# ESC_30A.net
KiCad netlist of a schematic drawn in Altium Designer
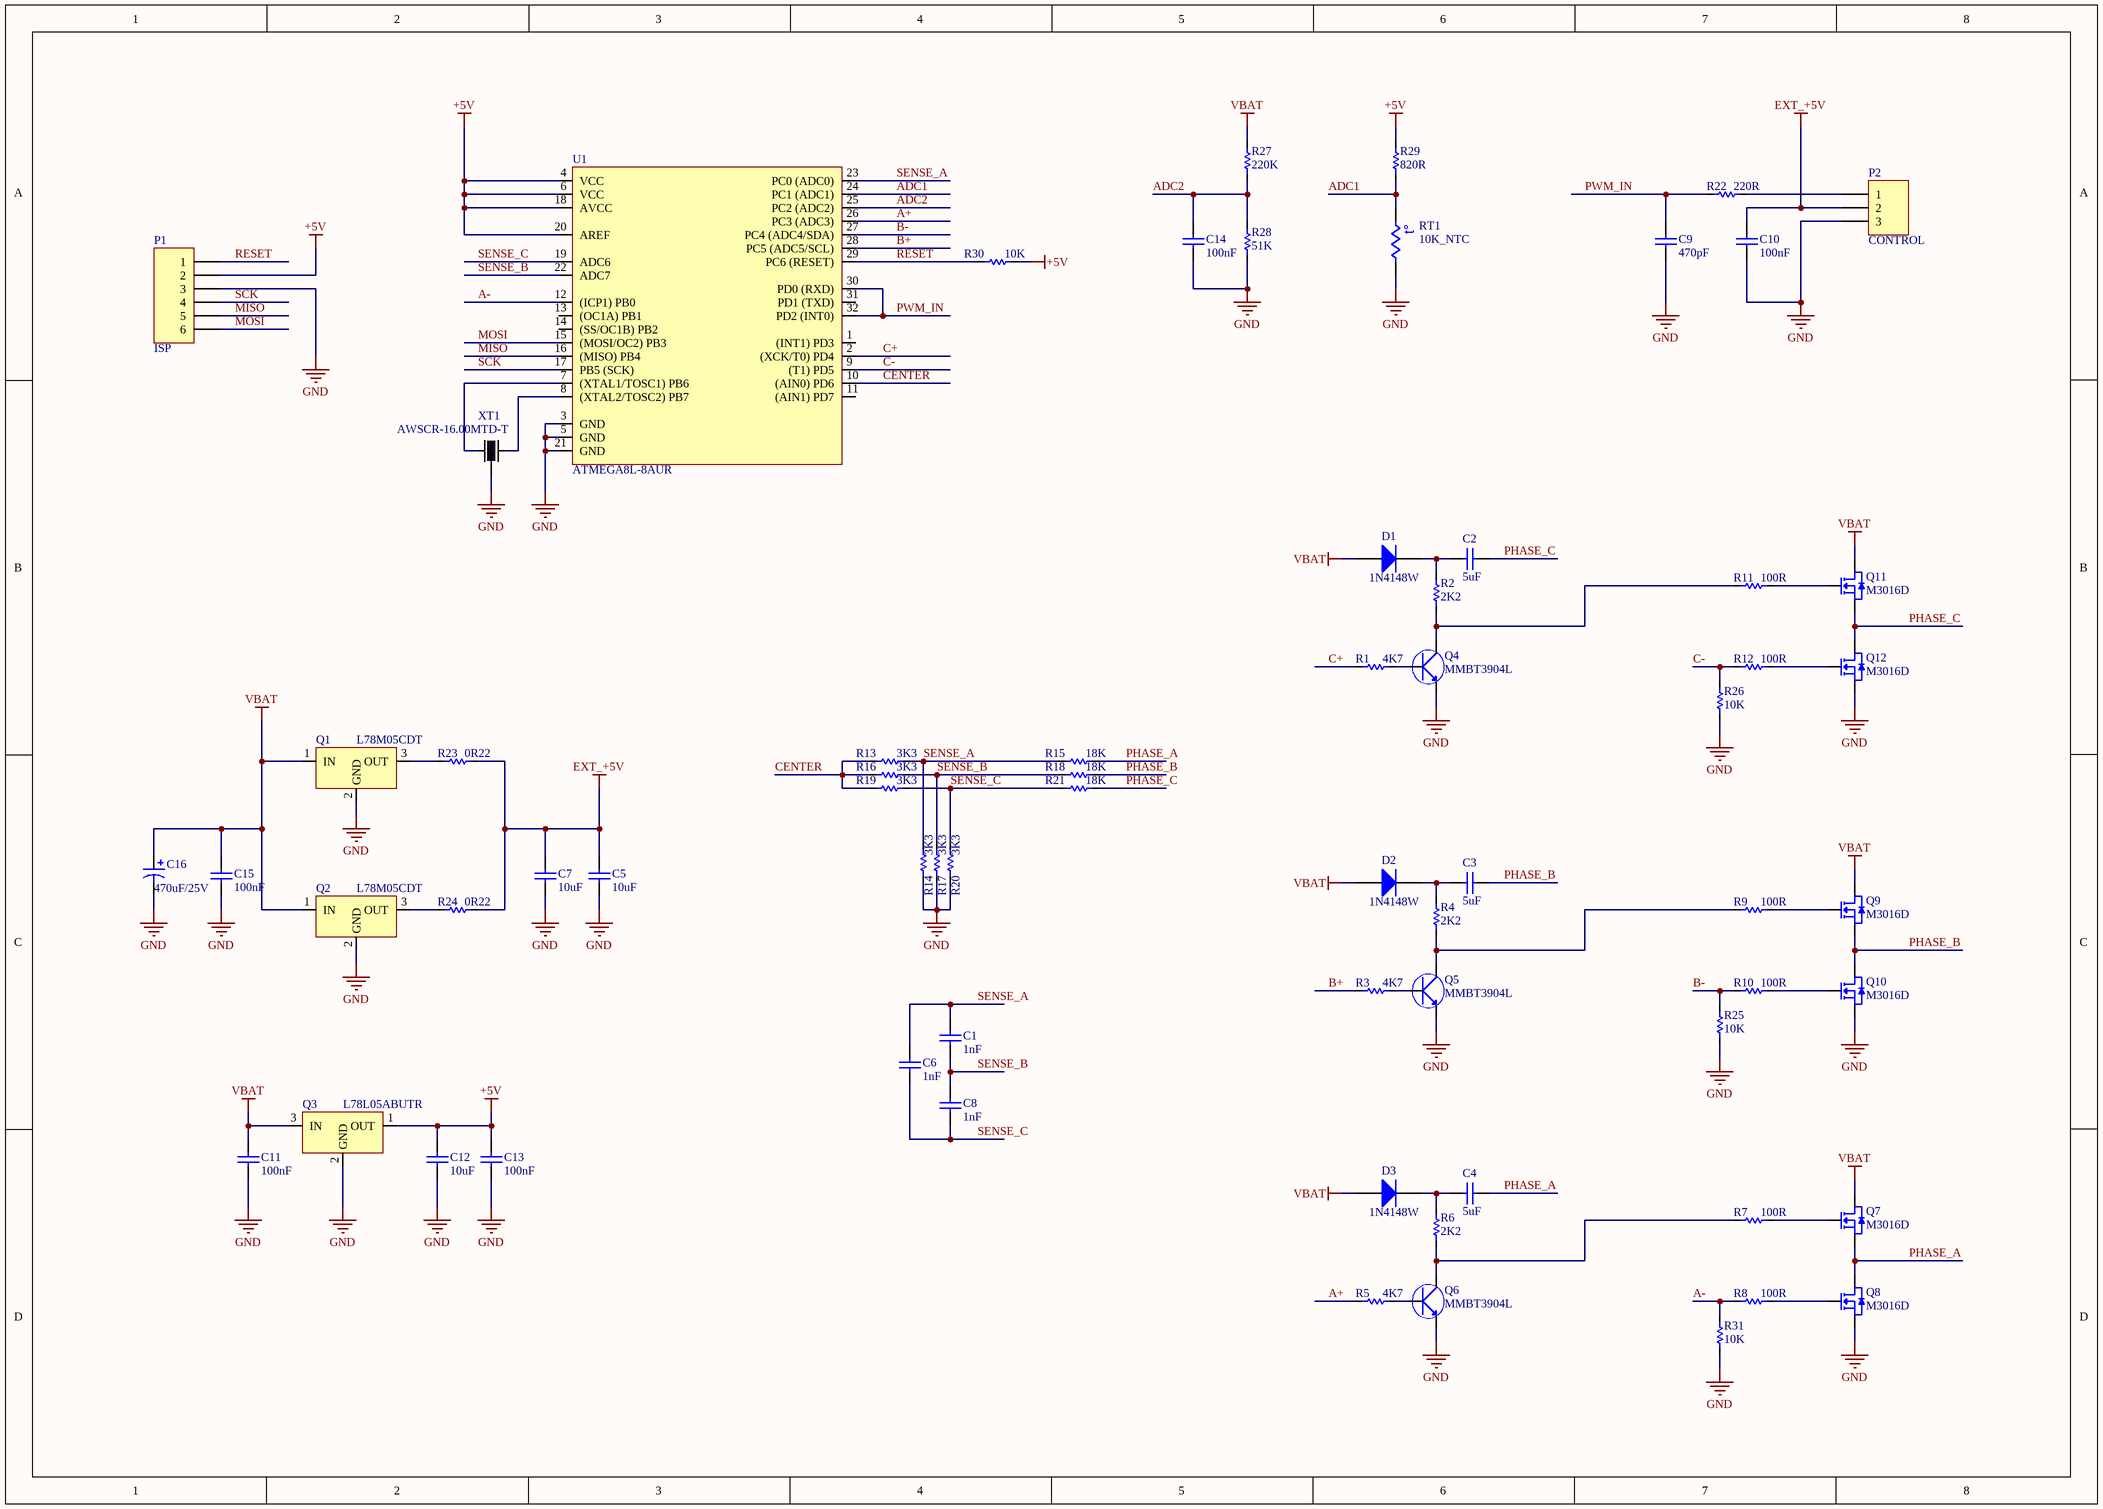
[diagram p0: ESC_30A.SchDoc]

(export (version "E")
  (design (tool "Eeschema 10.0.6"))
  (components
    (comp (ref "C1")
      (value "1nF")
      (footprint "C0603(1608)")
      (description "Capacitor")
      (libsource (lib "Miscellaneous Devices") (part "Cap"))
    )
    (comp (ref "C2")
      (value "5uF")
      (footprint "C1206(3216)")
      (description "Capacitor")
      (libsource (lib "Miscellaneous Devices") (part "Cap"))
    )
    (comp (ref "C3")
      (value "5uF")
      (footprint "C1206(3216)")
      (description "Capacitor")
      (libsource (lib "Miscellaneous Devices") (part "Cap"))
    )
    (comp (ref "C4")
      (value "5uF")
      (footprint "C1206(3216)")
      (description "Capacitor")
      (libsource (lib "Miscellaneous Devices") (part "Cap"))
    )
    (comp (ref "C5")
      (value "10uF")
      (footprint "C1206(3216)")
      (description "Capacitor")
      (libsource (lib "Miscellaneous Devices") (part "Cap"))
    )
    (comp (ref "C6")
      (value "1nF")
      (footprint "C0603(1608)")
      (description "Capacitor")
      (libsource (lib "Miscellaneous Devices") (part "Cap"))
    )
    (comp (ref "C7")
      (value "10uF")
      (footprint "C1206(3216)")
      (description "Capacitor")
      (libsource (lib "Miscellaneous Devices") (part "Cap"))
    )
    (comp (ref "C8")
      (value "1nF")
      (footprint "C0603(1608)")
      (description "Capacitor")
      (libsource (lib "Miscellaneous Devices") (part "Cap"))
    )
    (comp (ref "C9")
      (value "470pF")
      (footprint "C0603(1608)")
      (description "Capacitor")
      (libsource (lib "Miscellaneous Devices") (part "Cap"))
    )
    (comp (ref "C10")
      (value "100nF")
      (footprint "C0603(1608)")
      (description "Capacitor")
      (libsource (lib "Miscellaneous Devices") (part "Cap"))
    )
    (comp (ref "C11")
      (value "100nF")
      (footprint "C0603(1608)")
      (description "Capacitor")
      (libsource (lib "Miscellaneous Devices") (part "Cap"))
    )
    (comp (ref "C12")
      (value "10uF")
      (footprint "C1206(3216)")
      (description "Capacitor")
      (libsource (lib "Miscellaneous Devices") (part "Cap"))
    )
    (comp (ref "C13")
      (value "100nF")
      (footprint "C0603(1608)")
      (description "Capacitor")
      (libsource (lib "Miscellaneous Devices") (part "Cap"))
    )
    (comp (ref "C14")
      (value "100nF")
      (footprint "C0603(1608)")
      (description "Capacitor")
      (libsource (lib "Miscellaneous Devices") (part "Cap"))
    )
    (comp (ref "C15")
      (value "100nF")
      (footprint "C0603(1608)")
      (description "Capacitor")
      (libsource (lib "Miscellaneous Devices") (part "Cap"))
    )
    (comp (ref "C16")
      (value "470uF/25V")
      (footprint "RB.2/.4N")
      (description "CAP ALUM 470UF 20% 25V RADIAL")
      (libsource (lib "Miscellaneous Devices") (part "Cap Pol1"))
    )
    (comp (ref "D1")
      (value "1N4148W")
      (footprint "DIOMELF3515N")
      (description "Default Diode")
      (fields (field (name "PUBLISHER") "Altium Limited"))
      (libsource (lib "Miscellaneous Devices") (part "Diode"))
    )
    (comp (ref "D2")
      (value "1N4148W")
      (footprint "DIOMELF3515N")
      (description "Default Diode")
      (fields (field (name "PUBLISHER") "Altium Limited"))
      (libsource (lib "Miscellaneous Devices") (part "Diode"))
    )
    (comp (ref "D3")
      (value "1N4148W")
      (footprint "DIOMELF3515N")
      (description "Default Diode")
      (fields (field (name "PUBLISHER") "Altium Limited"))
      (libsource (lib "Miscellaneous Devices") (part "Diode"))
    )
    (comp (ref "P1")
      (value "ISP")
      (footprint "SWD-PAD_6")
      (description "Header, 6-Pin")
      (fields (field (name "PUBLISHER") "Altium Limited"))
      (libsource (lib "Miscellaneous Connectors") (part "Header 6"))
    )
    (comp (ref "P2")
      (value "CONTROL")
      (footprint "Pin Header 1x3 TH Pitch 2.54mm")
      (description "Header, 3-Pin")
      (fields (field (name "PUBLISHER") "Altium Limited"))
      (libsource (lib "Miscellaneous Connectors") (part "Header 3"))
    )
    (comp (ref "Q1")
      (value "L78M05CDT")
      (footprint "DPAK229P1010X238-3N")
      (description "IC REG LINEAR 5V 500MA DPAK")
      (libsource (lib "ali_lib") (part "78M05"))
    )
    (comp (ref "Q2")
      (value "L78M05CDT")
      (footprint "DPAK229P1010X238-3N")
      (description "IC REG LINEAR 5V 500MA DPAK")
      (libsource (lib "ali_lib") (part "78M05"))
    )
    (comp (ref "Q3")
      (value "L78L05ABUTR")
      (footprint "SOT89-150P409X160-3N")
      (description "IC REG LINEAR 5V 100MA SOT89-3")
      (libsource (lib "ali_lib") (part "78L05"))
    )
    (comp (ref "Q4")
      (value "MMBT3904L")
      (footprint "SOT23-A")
      (description "TRANS NPN 40V 0.2A SOT23")
      (libsource (lib "ali_lib") (part "TRANS"))
    )
    (comp (ref "Q5")
      (value "MMBT3904L")
      (footprint "SOT23-A")
      (description "TRANS NPN 40V 0.2A SOT23")
      (libsource (lib "ali_lib") (part "TRANS"))
    )
    (comp (ref "Q6")
      (value "MMBT3904L")
      (footprint "SOT23-A")
      (description "TRANS NPN 40V 0.2A SOT23")
      (libsource (lib "ali_lib") (part "TRANS"))
    )
    (comp (ref "Q7")
      (value "M3016D")
      (footprint "DPAK229P1010X238-3N")
      (description "N-Ch 30V Fast Switching MOSFETs")
      (libsource (lib "ali_lib") (part "MOSFET-M3016D"))
    )
    (comp (ref "Q8")
      (value "M3016D")
      (footprint "DPAK229P1010X238-3N")
      (description "N-Ch 30V Fast Switching MOSFETs")
      (libsource (lib "ali_lib") (part "MOSFET-M3016D"))
    )
    (comp (ref "Q9")
      (value "M3016D")
      (footprint "DPAK229P1010X238-3N")
      (description "N-Ch 30V Fast Switching MOSFETs")
      (libsource (lib "ali_lib") (part "MOSFET-M3016D"))
    )
    (comp (ref "Q10")
      (value "M3016D")
      (footprint "DPAK229P1010X238-3N")
      (description "N-Ch 30V Fast Switching MOSFETs")
      (libsource (lib "ali_lib") (part "MOSFET-M3016D"))
    )
    (comp (ref "Q11")
      (value "M3016D")
      (footprint "DPAK229P1010X238-3N")
      (description "N-Ch 30V Fast Switching MOSFETs")
      (libsource (lib "ali_lib") (part "MOSFET-M3016D"))
    )
    (comp (ref "Q12")
      (value "M3016D")
      (footprint "DPAK229P1010X238-3N")
      (description "N-Ch 30V Fast Switching MOSFETs")
      (libsource (lib "ali_lib") (part "MOSFET-M3016D"))
    )
    (comp (ref "R1")
      (value "4K7")
      (footprint "R0603(1608)")
      (description "Resistor")
      (libsource (lib "ali_lib") (part "R"))
    )
    (comp (ref "R2")
      (value "2K2")
      (footprint "R0603(1608)")
      (description "Resistor")
      (libsource (lib "ali_lib") (part "R"))
    )
    (comp (ref "R3")
      (value "4K7")
      (footprint "R0603(1608)")
      (description "Resistor")
      (libsource (lib "ali_lib") (part "R"))
    )
    (comp (ref "R4")
      (value "2K2")
      (footprint "R0603(1608)")
      (description "Resistor")
      (libsource (lib "ali_lib") (part "R"))
    )
    (comp (ref "R5")
      (value "4K7")
      (footprint "R0603(1608)")
      (description "Resistor")
      (libsource (lib "ali_lib") (part "R"))
    )
    (comp (ref "R6")
      (value "2K2")
      (footprint "R0603(1608)")
      (description "Resistor")
      (libsource (lib "ali_lib") (part "R"))
    )
    (comp (ref "R7")
      (value "100R")
      (footprint "R0603(1608)")
      (description "Resistor")
      (libsource (lib "ali_lib") (part "R"))
    )
    (comp (ref "R8")
      (value "100R")
      (footprint "R0603(1608)")
      (description "Resistor")
      (libsource (lib "ali_lib") (part "R"))
    )
    (comp (ref "R9")
      (value "100R")
      (footprint "R0603(1608)")
      (description "Resistor")
      (libsource (lib "ali_lib") (part "R"))
    )
    (comp (ref "R10")
      (value "100R")
      (footprint "R0603(1608)")
      (description "Resistor")
      (libsource (lib "ali_lib") (part "R"))
    )
    (comp (ref "R11")
      (value "100R")
      (footprint "R0603(1608)")
      (description "Resistor")
      (libsource (lib "ali_lib") (part "R"))
    )
    (comp (ref "R12")
      (value "100R")
      (footprint "R0603(1608)")
      (description "Resistor")
      (libsource (lib "ali_lib") (part "R"))
    )
    (comp (ref "R13")
      (value "3K3")
      (footprint "R0603(1608)")
      (description "Resistor")
      (libsource (lib "ali_lib") (part "R"))
    )
    (comp (ref "R14")
      (value "3K3")
      (footprint "R0603(1608)")
      (description "Resistor")
      (libsource (lib "ali_lib") (part "R"))
    )
    (comp (ref "R15")
      (value "18K")
      (footprint "R0603(1608)")
      (description "Resistor")
      (libsource (lib "ali_lib") (part "R"))
    )
    (comp (ref "R16")
      (value "3K3")
      (footprint "R0603(1608)")
      (description "Resistor")
      (libsource (lib "ali_lib") (part "R"))
    )
    (comp (ref "R17")
      (value "3K3")
      (footprint "R0603(1608)")
      (description "Resistor")
      (libsource (lib "ali_lib") (part "R"))
    )
    (comp (ref "R18")
      (value "18K")
      (footprint "R0603(1608)")
      (description "Resistor")
      (libsource (lib "ali_lib") (part "R"))
    )
    (comp (ref "R19")
      (value "3K3")
      (footprint "R0603(1608)")
      (description "Resistor")
      (libsource (lib "ali_lib") (part "R"))
    )
    (comp (ref "R20")
      (value "3K3")
      (footprint "R0603(1608)")
      (description "Resistor")
      (libsource (lib "ali_lib") (part "R"))
    )
    (comp (ref "R21")
      (value "18K")
      (footprint "R0603(1608)")
      (description "Resistor")
      (libsource (lib "ali_lib") (part "R"))
    )
    (comp (ref "R22")
      (value "220R")
      (footprint "R0603(1608)")
      (description "Resistor")
      (libsource (lib "ali_lib") (part "R"))
    )
    (comp (ref "R23")
      (value "0R22")
      (footprint "R0805(2012)")
      (description "Resistor")
      (libsource (lib "ali_lib") (part "R"))
    )
    (comp (ref "R24")
      (value "0R22")
      (footprint "R0805(2012)")
      (description "Resistor")
      (libsource (lib "ali_lib") (part "R"))
    )
    (comp (ref "R25")
      (value "10K")
      (footprint "R0603(1608)")
      (description "Resistor")
      (libsource (lib "ali_lib") (part "R"))
    )
    (comp (ref "R26")
      (value "10K")
      (footprint "R0603(1608)")
      (description "Resistor")
      (libsource (lib "ali_lib") (part "R"))
    )
    (comp (ref "R27")
      (value "220K")
      (footprint "R0603(1608)")
      (description "Resistor")
      (libsource (lib "ali_lib") (part "R"))
    )
    (comp (ref "R28")
      (value "51K")
      (footprint "R0603(1608)")
      (description "Resistor")
      (libsource (lib "ali_lib") (part "R"))
    )
    (comp (ref "R29")
      (value "820R")
      (footprint "R0603(1608)")
      (description "Resistor")
      (libsource (lib "ali_lib") (part "R"))
    )
    (comp (ref "R30")
      (value "10K")
      (footprint "R0603(1608)")
      (description "Resistor")
      (libsource (lib "ali_lib") (part "R"))
    )
    (comp (ref "R31")
      (value "10K")
      (footprint "R0603(1608)")
      (description "Resistor")
      (libsource (lib "ali_lib") (part "R"))
    )
    (comp (ref "RT1")
      (value "10K_NTC")
      (footprint "R0805(2012)")
      (description "Thermistor")
      (fields (field (name "PUBLISHER") "Altium Limited"))
      (libsource (lib "Miscellaneous Devices") (part "Res Thermal"))
    )
    (comp (ref "U1")
      (value "ATMEGA8L-8AUR")
      (footprint "TQFP80P900X900X120-32N")
      (description "IC MCU 8BIT 8KB FLASH 32TQFP")
      (libsource (lib "ali_lib") (part "ATMEGA8L"))
    )
    (comp (ref "XT1")
      (value "AWSCR-16.00MTD-T")
      (footprint "XTAL_AWSCR")
      (description "CER RES 16.0000MHZ 22PF SMD")
      (libsource (lib "ali_lib") (part "XTAL_RESONATOR"))
    )
  )
  (nets
    (net (code "1") (name "+5V") (class "Default")
      (node (ref "C12") (pin "2") (pinfunction "2_2") (pintype "passive"))
      (node (ref "C13") (pin "2") (pinfunction "2_2") (pintype "passive"))
      (node (ref "P1") (pin "2") (pinfunction "2_2") (pintype "passive"))
      (node (ref "Q3") (pin "1") (pinfunction "OUT_1") (pintype "passive"))
      (node (ref "R29") (pin "2") (pinfunction "2_2") (pintype "passive"))
      (node (ref "R30") (pin "2") (pinfunction "2_2") (pintype "passive"))
      (node (ref "U1") (pin "18") (pinfunction "AVCC_18") (pintype "passive"))
      (node (ref "U1") (pin "20") (pinfunction "AREF_20") (pintype "passive"))
      (node (ref "U1") (pin "4") (pinfunction "VCC_4") (pintype "passive"))
      (node (ref "U1") (pin "6") (pinfunction "VCC_6") (pintype "passive"))
    )
    (net (code "2") (name "/A+") (class "Default")
      (node (ref "R5") (pin "1") (pinfunction "1_1") (pintype "passive"))
      (node (ref "U1") (pin "26") (pinfunction "PC3_(ADC3)_26") (pintype "passive"))
    )
    (net (code "3") (name "/A-") (class "Default")
      (node (ref "R31") (pin "1") (pinfunction "1_1") (pintype "passive"))
      (node (ref "R8") (pin "1") (pinfunction "1_1") (pintype "passive"))
      (node (ref "U1") (pin "12") (pinfunction "(ICP1)_PB0_12") (pintype "passive"))
    )
    (net (code "4") (name "/ADC1") (class "Default")
      (node (ref "R29") (pin "1") (pinfunction "1_1") (pintype "passive"))
      (node (ref "RT1") (pin "1") (pinfunction "1_1") (pintype "passive"))
      (node (ref "U1") (pin "24") (pinfunction "PC1_(ADC1)_24") (pintype "passive"))
    )
    (net (code "5") (name "/ADC2") (class "Default")
      (node (ref "C14") (pin "2") (pinfunction "2_2") (pintype "passive"))
      (node (ref "R27") (pin "1") (pinfunction "1_1") (pintype "passive"))
      (node (ref "R28") (pin "2") (pinfunction "2_2") (pintype "passive"))
      (node (ref "U1") (pin "25") (pinfunction "PC2_(ADC2)_25") (pintype "passive"))
    )
    (net (code "6") (name "/B+") (class "Default")
      (node (ref "R3") (pin "1") (pinfunction "1_1") (pintype "passive"))
      (node (ref "U1") (pin "28") (pinfunction "PC5_(ADC5/SCL)_28") (pintype "passive"))
    )
    (net (code "7") (name "/B-") (class "Default")
      (node (ref "R10") (pin "1") (pinfunction "1_1") (pintype "passive"))
      (node (ref "R25") (pin "1") (pinfunction "1_1") (pintype "passive"))
      (node (ref "U1") (pin "27") (pinfunction "PC4_(ADC4/SDA)_27") (pintype "passive"))
    )
    (net (code "8") (name "/C+") (class "Default")
      (node (ref "R1") (pin "1") (pinfunction "1_1") (pintype "passive"))
      (node (ref "U1") (pin "2") (pinfunction "(XCK/T0)_PD4_2") (pintype "passive"))
    )
    (net (code "9") (name "/C-") (class "Default")
      (node (ref "R12") (pin "1") (pinfunction "1_1") (pintype "passive"))
      (node (ref "R26") (pin "1") (pinfunction "1_1") (pintype "passive"))
      (node (ref "U1") (pin "9") (pinfunction "(T1)_PD5_9") (pintype "passive"))
    )
    (net (code "10") (name "/CENTER") (class "Default")
      (node (ref "R13") (pin "1") (pinfunction "1_1") (pintype "passive"))
      (node (ref "R16") (pin "1") (pinfunction "1_1") (pintype "passive"))
      (node (ref "R19") (pin "1") (pinfunction "1_1") (pintype "passive"))
      (node (ref "U1") (pin "10") (pinfunction "(AIN0)_PD6_10") (pintype "passive"))
    )
    (net (code "11") (name "/MISO") (class "Default")
      (node (ref "P1") (pin "5") (pinfunction "5_5") (pintype "passive"))
      (node (ref "U1") (pin "16") (pinfunction "(MISO)_PB4_16") (pintype "passive"))
    )
    (net (code "12") (name "/MOSI") (class "Default")
      (node (ref "P1") (pin "6") (pinfunction "6_6") (pintype "passive"))
      (node (ref "U1") (pin "15") (pinfunction "(MOSI/OC2)_PB3_15") (pintype "passive"))
    )
    (net (code "13") (name "/PHASE_A") (class "Default")
      (node (ref "C4") (pin "1") (pinfunction "1_1") (pintype "passive"))
      (node (ref "Q7") (pin "3") (pinfunction "S_3") (pintype "passive"))
      (node (ref "Q8") (pin "2") (pinfunction "D_2") (pintype "passive"))
      (node (ref "R15") (pin "1") (pinfunction "1_1") (pintype "passive"))
    )
    (net (code "14") (name "/PHASE_B") (class "Default")
      (node (ref "C3") (pin "1") (pinfunction "1_1") (pintype "passive"))
      (node (ref "Q10") (pin "2") (pinfunction "D_2") (pintype "passive"))
      (node (ref "Q9") (pin "3") (pinfunction "S_3") (pintype "passive"))
      (node (ref "R18") (pin "1") (pinfunction "1_1") (pintype "passive"))
    )
    (net (code "15") (name "/PHASE_C") (class "Default")
      (node (ref "C2") (pin "1") (pinfunction "1_1") (pintype "passive"))
      (node (ref "Q11") (pin "3") (pinfunction "S_3") (pintype "passive"))
      (node (ref "Q12") (pin "2") (pinfunction "D_2") (pintype "passive"))
      (node (ref "R21") (pin "1") (pinfunction "1_1") (pintype "passive"))
    )
    (net (code "16") (name "/PWM_IN") (class "Default")
      (node (ref "C9") (pin "2") (pinfunction "2_2") (pintype "passive"))
      (node (ref "R22") (pin "1") (pinfunction "1_1") (pintype "passive"))
      (node (ref "U1") (pin "30") (pinfunction "PD0_(RXD)_30") (pintype "passive"))
      (node (ref "U1") (pin "32") (pinfunction "PD2_(INT0)_32") (pintype "passive"))
    )
    (net (code "17") (name "/RESET") (class "Default")
      (node (ref "P1") (pin "1") (pinfunction "1_1") (pintype "passive"))
      (node (ref "R30") (pin "1") (pinfunction "1_1") (pintype "passive"))
      (node (ref "U1") (pin "29") (pinfunction "PC6_(RESET)_29") (pintype "passive"))
    )
    (net (code "18") (name "/SCK") (class "Default")
      (node (ref "P1") (pin "4") (pinfunction "4_4") (pintype "passive"))
      (node (ref "U1") (pin "17") (pinfunction "PB5_(SCK)_17") (pintype "passive"))
    )
    (net (code "19") (name "/SENSE_A") (class "Default")
      (node (ref "C1") (pin "1") (pinfunction "1_1") (pintype "passive"))
      (node (ref "C6") (pin "1") (pinfunction "1_1") (pintype "passive"))
      (node (ref "R13") (pin "2") (pinfunction "2_2") (pintype "passive"))
      (node (ref "R14") (pin "2") (pinfunction "2_2") (pintype "passive"))
      (node (ref "R15") (pin "2") (pinfunction "2_2") (pintype "passive"))
      (node (ref "U1") (pin "23") (pinfunction "PC0_(ADC0)_23") (pintype "passive"))
    )
    (net (code "20") (name "/SENSE_B") (class "Default")
      (node (ref "C1") (pin "2") (pinfunction "2_2") (pintype "passive"))
      (node (ref "C8") (pin "1") (pinfunction "1_1") (pintype "passive"))
      (node (ref "R16") (pin "2") (pinfunction "2_2") (pintype "passive"))
      (node (ref "R17") (pin "2") (pinfunction "2_2") (pintype "passive"))
      (node (ref "R18") (pin "2") (pinfunction "2_2") (pintype "passive"))
      (node (ref "U1") (pin "22") (pinfunction "ADC7_22") (pintype "passive"))
    )
    (net (code "21") (name "/SENSE_C") (class "Default")
      (node (ref "C6") (pin "2") (pinfunction "2_2") (pintype "passive"))
      (node (ref "C8") (pin "2") (pinfunction "2_2") (pintype "passive"))
      (node (ref "R19") (pin "2") (pinfunction "2_2") (pintype "passive"))
      (node (ref "R20") (pin "2") (pinfunction "2_2") (pintype "passive"))
      (node (ref "R21") (pin "2") (pinfunction "2_2") (pintype "passive"))
      (node (ref "U1") (pin "19") (pinfunction "ADC6_19") (pintype "passive"))
    )
    (net (code "22") (name "EXT_+5V") (class "Default")
      (node (ref "C10") (pin "2") (pinfunction "2_2") (pintype "passive"))
      (node (ref "C5") (pin "2") (pinfunction "2_2") (pintype "passive"))
      (node (ref "C7") (pin "2") (pinfunction "2_2") (pintype "passive"))
      (node (ref "P2") (pin "2") (pinfunction "2_2") (pintype "passive"))
      (node (ref "R23") (pin "2") (pinfunction "2_2") (pintype "passive"))
      (node (ref "R24") (pin "2") (pinfunction "2_2") (pintype "passive"))
    )
    (net (code "23") (name "GND") (class "Default")
      (node (ref "C10") (pin "1") (pinfunction "1_1") (pintype "passive"))
      (node (ref "C11") (pin "1") (pinfunction "1_1") (pintype "passive"))
      (node (ref "C12") (pin "1") (pinfunction "1_1") (pintype "passive"))
      (node (ref "C13") (pin "1") (pinfunction "1_1") (pintype "passive"))
      (node (ref "C14") (pin "1") (pinfunction "1_1") (pintype "passive"))
      (node (ref "C15") (pin "1") (pinfunction "1_1") (pintype "passive"))
      (node (ref "C16") (pin "2") (pinfunction "2_2") (pintype "passive"))
      (node (ref "C5") (pin "1") (pinfunction "1_1") (pintype "passive"))
      (node (ref "C7") (pin "1") (pinfunction "1_1") (pintype "passive"))
      (node (ref "C9") (pin "1") (pinfunction "1_1") (pintype "passive"))
      (node (ref "P1") (pin "3") (pinfunction "3_3") (pintype "passive"))
      (node (ref "P2") (pin "3") (pinfunction "3_3") (pintype "passive"))
      (node (ref "Q1") (pin "2") (pinfunction "GND_2") (pintype "passive"))
      (node (ref "Q10") (pin "3") (pinfunction "S_3") (pintype "passive"))
      (node (ref "Q12") (pin "3") (pinfunction "S_3") (pintype "passive"))
      (node (ref "Q2") (pin "2") (pinfunction "GND_2") (pintype "passive"))
      (node (ref "Q3") (pin "2") (pinfunction "GND_2") (pintype "passive"))
      (node (ref "Q4") (pin "2") (pinfunction "E_2") (pintype "passive"))
      (node (ref "Q5") (pin "2") (pinfunction "E_2") (pintype "passive"))
      (node (ref "Q6") (pin "2") (pinfunction "E_2") (pintype "passive"))
      (node (ref "Q8") (pin "3") (pinfunction "S_3") (pintype "passive"))
      (node (ref "R14") (pin "1") (pinfunction "1_1") (pintype "passive"))
      (node (ref "R17") (pin "1") (pinfunction "1_1") (pintype "passive"))
      (node (ref "R20") (pin "1") (pinfunction "1_1") (pintype "passive"))
      (node (ref "R25") (pin "2") (pinfunction "2_2") (pintype "passive"))
      (node (ref "R26") (pin "2") (pinfunction "2_2") (pintype "passive"))
      (node (ref "R28") (pin "1") (pinfunction "1_1") (pintype "passive"))
      (node (ref "R31") (pin "2") (pinfunction "2_2") (pintype "passive"))
      (node (ref "RT1") (pin "2") (pinfunction "2_2") (pintype "passive"))
      (node (ref "U1") (pin "21") (pinfunction "GND_21") (pintype "passive"))
      (node (ref "U1") (pin "3") (pinfunction "GND_3") (pintype "passive"))
      (node (ref "U1") (pin "5") (pinfunction "GND_5") (pintype "passive"))
      (node (ref "XT1") (pin "2") (pinfunction "2_2") (pintype "passive"))
    )
    (net (code "24") (name "Net-(D1-K)") (class "Default")
      (node (ref "C2") (pin "2") (pinfunction "2_2") (pintype "passive"))
      (node (ref "D1") (pin "1") (pinfunction "K_1") (pintype "passive"))
      (node (ref "R2") (pin "1") (pinfunction "1_1") (pintype "passive"))
    )
    (net (code "25") (name "Net-(D2-K)") (class "Default")
      (node (ref "C3") (pin "2") (pinfunction "2_2") (pintype "passive"))
      (node (ref "D2") (pin "1") (pinfunction "K_1") (pintype "passive"))
      (node (ref "R4") (pin "1") (pinfunction "1_1") (pintype "passive"))
    )
    (net (code "26") (name "Net-(D3-K)") (class "Default")
      (node (ref "C4") (pin "2") (pinfunction "2_2") (pintype "passive"))
      (node (ref "D3") (pin "1") (pinfunction "K_1") (pintype "passive"))
      (node (ref "R6") (pin "1") (pinfunction "1_1") (pintype "passive"))
    )
    (net (code "27") (name "Net-(P2-Pad1)") (class "Default")
      (node (ref "P2") (pin "1") (pinfunction "1_1") (pintype "passive"))
      (node (ref "R22") (pin "2") (pinfunction "2_2") (pintype "passive"))
    )
    (net (code "28") (name "Net-(Q1-OUT)") (class "Default")
      (node (ref "Q1") (pin "3") (pinfunction "OUT_3") (pintype "passive"))
      (node (ref "R23") (pin "1") (pinfunction "1_1") (pintype "passive"))
    )
    (net (code "29") (name "Net-(Q2-OUT)") (class "Default")
      (node (ref "Q2") (pin "3") (pinfunction "OUT_3") (pintype "passive"))
      (node (ref "R24") (pin "1") (pinfunction "1_1") (pintype "passive"))
    )
    (net (code "30") (name "Net-(Q4-B)") (class "Default")
      (node (ref "Q4") (pin "1") (pinfunction "B_1") (pintype "passive"))
      (node (ref "R1") (pin "2") (pinfunction "2_2") (pintype "passive"))
    )
    (net (code "31") (name "Net-(Q4-C)") (class "Default")
      (node (ref "Q4") (pin "3") (pinfunction "C_3") (pintype "passive"))
      (node (ref "R11") (pin "1") (pinfunction "1_1") (pintype "passive"))
      (node (ref "R2") (pin "2") (pinfunction "2_2") (pintype "passive"))
    )
    (net (code "32") (name "Net-(Q5-B)") (class "Default")
      (node (ref "Q5") (pin "1") (pinfunction "B_1") (pintype "passive"))
      (node (ref "R3") (pin "2") (pinfunction "2_2") (pintype "passive"))
    )
    (net (code "33") (name "Net-(Q5-C)") (class "Default")
      (node (ref "Q5") (pin "3") (pinfunction "C_3") (pintype "passive"))
      (node (ref "R4") (pin "2") (pinfunction "2_2") (pintype "passive"))
      (node (ref "R9") (pin "1") (pinfunction "1_1") (pintype "passive"))
    )
    (net (code "34") (name "Net-(Q6-B)") (class "Default")
      (node (ref "Q6") (pin "1") (pinfunction "B_1") (pintype "passive"))
      (node (ref "R5") (pin "2") (pinfunction "2_2") (pintype "passive"))
    )
    (net (code "35") (name "Net-(Q6-C)") (class "Default")
      (node (ref "Q6") (pin "3") (pinfunction "C_3") (pintype "passive"))
      (node (ref "R6") (pin "2") (pinfunction "2_2") (pintype "passive"))
      (node (ref "R7") (pin "1") (pinfunction "1_1") (pintype "passive"))
    )
    (net (code "36") (name "Net-(Q7-G)") (class "Default")
      (node (ref "Q7") (pin "1") (pinfunction "G_1") (pintype "passive"))
      (node (ref "R7") (pin "2") (pinfunction "2_2") (pintype "passive"))
    )
    (net (code "37") (name "Net-(Q8-G)") (class "Default")
      (node (ref "Q8") (pin "1") (pinfunction "G_1") (pintype "passive"))
      (node (ref "R8") (pin "2") (pinfunction "2_2") (pintype "passive"))
    )
    (net (code "38") (name "Net-(Q9-G)") (class "Default")
      (node (ref "Q9") (pin "1") (pinfunction "G_1") (pintype "passive"))
      (node (ref "R9") (pin "2") (pinfunction "2_2") (pintype "passive"))
    )
    (net (code "39") (name "Net-(Q10-G)") (class "Default")
      (node (ref "Q10") (pin "1") (pinfunction "G_1") (pintype "passive"))
      (node (ref "R10") (pin "2") (pinfunction "2_2") (pintype "passive"))
    )
    (net (code "40") (name "Net-(Q11-G)") (class "Default")
      (node (ref "Q11") (pin "1") (pinfunction "G_1") (pintype "passive"))
      (node (ref "R11") (pin "2") (pinfunction "2_2") (pintype "passive"))
    )
    (net (code "41") (name "Net-(Q12-G)") (class "Default")
      (node (ref "Q12") (pin "1") (pinfunction "G_1") (pintype "passive"))
      (node (ref "R12") (pin "2") (pinfunction "2_2") (pintype "passive"))
    )
    (net (code "42") (name "Net-(U1-(XTAL1{slash}TOSC1)_PB6)") (class "Default")
      (node (ref "U1") (pin "7") (pinfunction "(XTAL1/TOSC1)_PB6_7") (pintype "passive"))
      (node (ref "XT1") (pin "1") (pinfunction "1_1") (pintype "passive"))
    )
    (net (code "43") (name "Net-(U1-(XTAL2{slash}TOSC2)_PB7)") (class "Default")
      (node (ref "U1") (pin "8") (pinfunction "(XTAL2/TOSC2)_PB7_8") (pintype "passive"))
      (node (ref "XT1") (pin "3") (pinfunction "3_3") (pintype "passive"))
    )
    (net (code "44") (name "VBAT") (class "Default")
      (node (ref "C11") (pin "2") (pinfunction "2_2") (pintype "passive"))
      (node (ref "C15") (pin "2") (pinfunction "2_2") (pintype "passive"))
      (node (ref "C16") (pin "1") (pinfunction "1_1") (pintype "passive"))
      (node (ref "D1") (pin "2") (pinfunction "A_2") (pintype "passive"))
      (node (ref "D2") (pin "2") (pinfunction "A_2") (pintype "passive"))
      (node (ref "D3") (pin "2") (pinfunction "A_2") (pintype "passive"))
      (node (ref "Q1") (pin "1") (pinfunction "IN_1") (pintype "passive"))
      (node (ref "Q11") (pin "2") (pinfunction "D_2") (pintype "passive"))
      (node (ref "Q2") (pin "1") (pinfunction "IN_1") (pintype "passive"))
      (node (ref "Q3") (pin "3") (pinfunction "IN_3") (pintype "passive"))
      (node (ref "Q7") (pin "2") (pinfunction "D_2") (pintype "passive"))
      (node (ref "Q9") (pin "2") (pinfunction "D_2") (pintype "passive"))
      (node (ref "R27") (pin "2") (pinfunction "2_2") (pintype "passive"))
    )
    (net (code "45") (name "unconnected-(U1-(AIN1)_PD7-Pad11)") (class "Default")
      (node (ref "U1") (pin "11") (pinfunction "(AIN1)_PD7_11") (pintype "passive"))
    )
    (net (code "46") (name "unconnected-(U1-(INT1)_PD3-Pad1)") (class "Default")
      (node (ref "U1") (pin "1") (pinfunction "(INT1)_PD3_1") (pintype "passive"))
    )
    (net (code "47") (name "unconnected-(U1-(OC1A)_PB1-Pad13)") (class "Default")
      (node (ref "U1") (pin "13") (pinfunction "(OC1A)_PB1_13") (pintype "passive"))
    )
    (net (code "48") (name "unconnected-(U1-(SS{slash}OC1B)_PB2-Pad14)") (class "Default")
      (node (ref "U1") (pin "14") (pinfunction "(SS/OC1B)_PB2_14") (pintype "passive"))
    )
    (net (code "49") (name "unconnected-(U1-PD1_(TXD)-Pad31)") (class "Default")
      (node (ref "U1") (pin "31") (pinfunction "PD1_(TXD)_31") (pintype "passive"))
    )
  )
)
